# untitled2.net
KiCad netlist of a schematic drawn in EAGLE
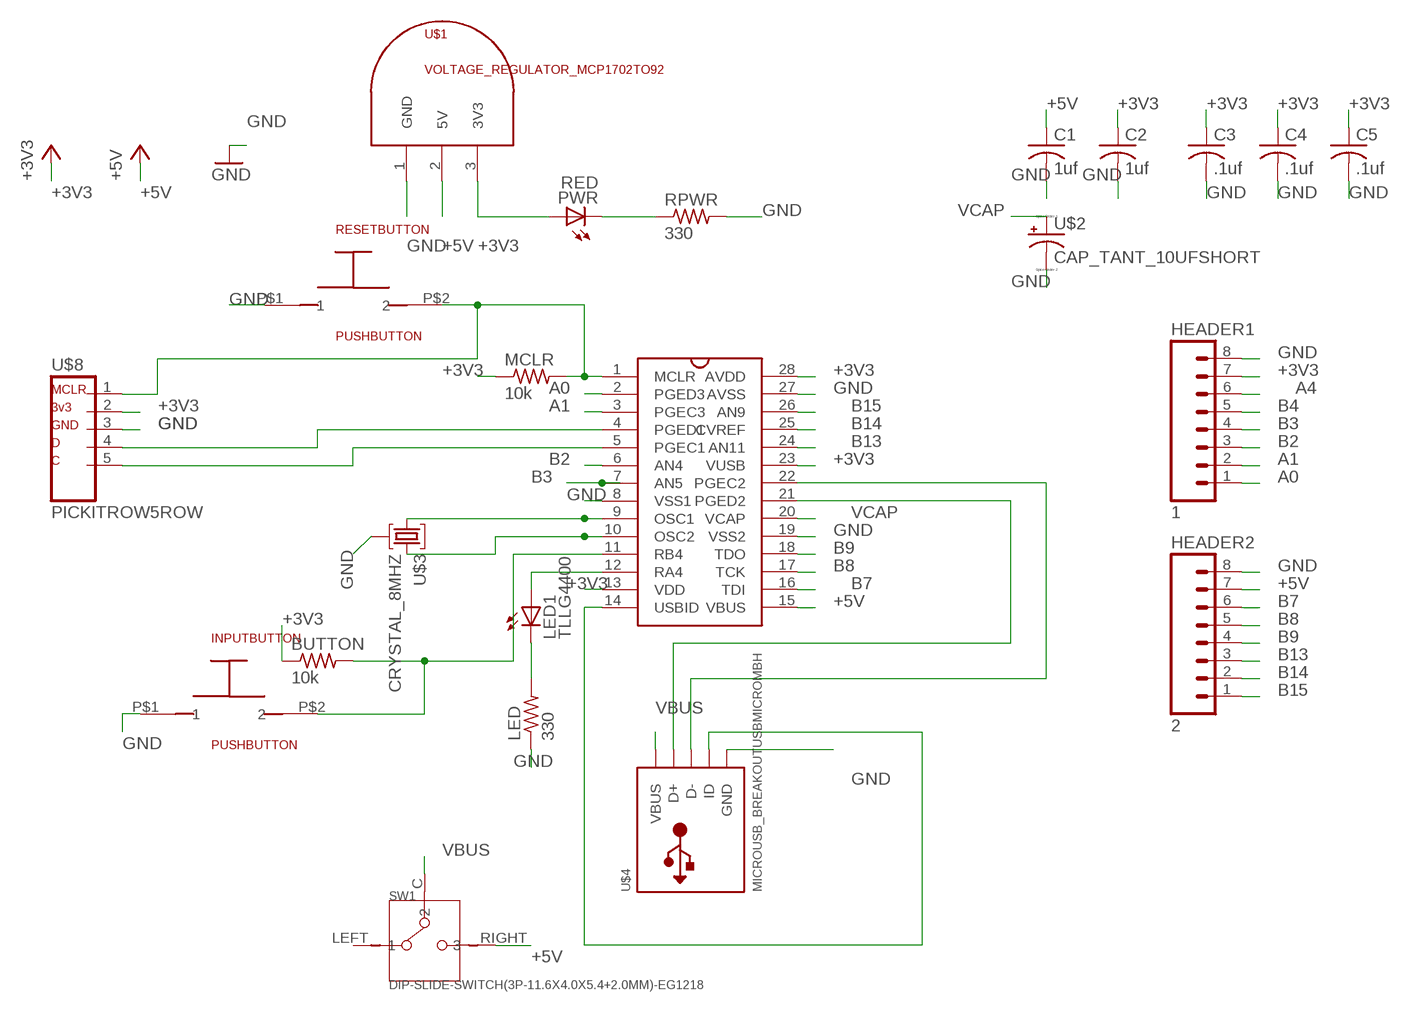
[diagram p0: schematic, sheet 1]

(export (version "E")
  (design (tool "Eeschema 10.0.6"))
  (components
    (comp (ref "BUTTON")
      (value "10k")
      (footprint "eagle-import:0207_10")
      (libsource (lib "eagle-import") (part "R-US_0207/10"))
    )
    (comp (ref "C1")
      (value "1uf")
      (footprint "eagle-import:C025-030X050")
      (libsource (lib "eagle-import") (part "C-US025-030X050"))
    )
    (comp (ref "C2")
      (value "1uf")
      (footprint "eagle-import:C025-030X050")
      (libsource (lib "eagle-import") (part "C-US025-030X050"))
    )
    (comp (ref "C3")
      (value ".1uf")
      (footprint "eagle-import:C025-030X050")
      (libsource (lib "eagle-import") (part "C-US025-030X050"))
    )
    (comp (ref "C4")
      (value ".1uf")
      (footprint "eagle-import:C025-030X050")
      (libsource (lib "eagle-import") (part "C-US025-030X050"))
    )
    (comp (ref "C5")
      (value ".1uf")
      (footprint "eagle-import:C025-030X050")
      (libsource (lib "eagle-import") (part "C-US025-030X050"))
    )
    (comp (ref "HEADER1")
      (value "1")
      (footprint "eagle-import:1X08_ROUND")
      (libsource (lib "eagle-import") (part "M08"))
    )
    (comp (ref "HEADER2")
      (value "2")
      (footprint "eagle-import:1X08_ROUND")
      (libsource (lib "eagle-import") (part "M08"))
    )
    (comp (ref "INPUTBUTTON")
      (value "PUSHBUTTON")
      (footprint "eagle-import:PUSHBUTTON")
      (libsource (lib "eagle-import") (part "PUSHBUTTON"))
    )
    (comp (ref "LED")
      (value "330")
      (footprint "eagle-import:0207_10")
      (libsource (lib "eagle-import") (part "R-US_0207/10"))
    )
    (comp (ref "LED1")
      (value "TLLG4400")
      (footprint "eagle-import:LED3MM")
      (fields (field (name "MF") "VISHAY SEMICONDUCTOR"))
      (libsource (lib "eagle-import") (part "TLLG4400"))
    )
    (comp (ref "MCLR")
      (value "10k")
      (footprint "eagle-import:0207_10")
      (libsource (lib "eagle-import") (part "R-US_0207/10"))
    )
    (comp (ref "PWR")
      (value "RED")
      (footprint "eagle-import:LED3MM")
      (libsource (lib "eagle-import") (part "LED3MM"))
    )
    (comp (ref "RESETBUTTON")
      (value "PUSHBUTTON")
      (footprint "eagle-import:PUSHBUTTON")
      (libsource (lib "eagle-import") (part "PUSHBUTTON"))
    )
    (comp (ref "RPWR")
      (value "330")
      (footprint "eagle-import:0207_10")
      (libsource (lib "eagle-import") (part "R-US_0207/10"))
    )
    (comp (ref "SW1")
      (value "DIP-SLIDE-SWITCH(3P-11.6X4.0X5.4+2.0MM)-EG1218")
      (footprint "eagle-import:SW3-2.5-11.6X4.0X5.4+2.0MM")
      (libsource (lib "eagle-import") (part "DIP-SLIDE-SWITCH(3P-11.6X4.0X5.4+2.0MM)-EG1218"))
    )
    (comp (ref "U$1")
      (value "VOLTAGE_REGULATOR_MCP1702TO92")
      (footprint "eagle-import:TO92")
      (libsource (lib "eagle-import") (part "VOLTAGE_REGULATOR_MCP1702TO92"))
    )
    (comp (ref "U$2")
      (value "CAP_TANT_10UFSHORT")
      (footprint "eagle-import:C025-040X050POL")
      (libsource (lib "eagle-import") (part "CAP_TANT_10UFSHORT"))
    )
    (comp (ref "U$3")
      (value "CRYSTAL_8MHZ")
      (footprint "eagle-import:CRYSTAL_8MHZ")
      (libsource (lib "eagle-import") (part "CRYSTAL_8MHZ"))
    )
    (comp (ref "U$4")
      (value "MICROUSB_BREAKOUTUSBMICROMBH")
      (footprint "eagle-import:USB-MB-H")
      (libsource (lib "eagle-import") (part "MICROUSB_BREAKOUTUSBMICROMBH"))
    )
    (comp (ref "U$5")
      (value "PIC32MX250F128B")
      (footprint "eagle-import:DIL28-3")
      (libsource (lib "eagle-import") (part "PIC32MX250F128B"))
    )
    (comp (ref "U$8")
      (value "PICKITROW5ROW")
      (footprint "eagle-import:1X05")
      (libsource (lib "eagle-import") (part "PICKITROW5ROW"))
    )
  )
  (nets
    (net (code "1") (name "+3V3") (class "Default")
      (node (ref "BUTTON") (pin "1") (pinfunction "1_1") (pintype "passive"))
      (node (ref "C2") (pin "1") (pinfunction "1_1") (pintype "passive"))
      (node (ref "C3") (pin "1") (pinfunction "1_1") (pintype "passive"))
      (node (ref "C4") (pin "1") (pinfunction "1_1") (pintype "passive"))
      (node (ref "C5") (pin "1") (pinfunction "1_1") (pintype "passive"))
      (node (ref "HEADER1") (pin "7") (pinfunction "7_7") (pintype "passive"))
      (node (ref "MCLR") (pin "1") (pinfunction "1_1") (pintype "passive"))
      (node (ref "PWR") (pin "A") (pinfunction "A_A") (pintype "passive"))
      (node (ref "U$1") (pin "3") (pinfunction "3V3_3") (pintype "bidirectional"))
      (node (ref "U$5") (pin "13") (pinfunction "VDD_13") (pintype "bidirectional"))
      (node (ref "U$5") (pin "23") (pinfunction "VUSB_23") (pintype "bidirectional"))
      (node (ref "U$5") (pin "28") (pinfunction "AVDD_28") (pintype "bidirectional"))
      (node (ref "U$8") (pin "2") (pinfunction "3V3_2") (pintype "passive"))
    )
    (net (code "2") (name "+5V") (class "Default")
      (node (ref "C1") (pin "1") (pinfunction "1_1") (pintype "passive"))
      (node (ref "HEADER2") (pin "7") (pinfunction "7_7") (pintype "passive"))
      (node (ref "SW1") (pin "RIGHT") (pinfunction "3_RIGHT") (pintype "bidirectional"))
      (node (ref "U$1") (pin "2") (pinfunction "5V_2") (pintype "bidirectional"))
      (node (ref "U$5") (pin "15") (pinfunction "VBUS_15") (pintype "bidirectional"))
    )
    (net (code "3") (name "/A0") (class "Default")
      (node (ref "HEADER1") (pin "1") (pinfunction "1_1") (pintype "passive"))
      (node (ref "U$5") (pin "2") (pinfunction "PGED3_2") (pintype "bidirectional"))
    )
    (net (code "4") (name "/A1") (class "Default")
      (node (ref "HEADER1") (pin "2") (pinfunction "2_2") (pintype "passive"))
      (node (ref "U$5") (pin "3") (pinfunction "PGEC3_3") (pintype "bidirectional"))
    )
    (net (code "5") (name "/A4") (class "Default")
      (node (ref "HEADER1") (pin "6") (pinfunction "6_6") (pintype "passive"))
      (node (ref "LED1") (pin "A") (pinfunction "A_A") (pintype "passive"))
      (node (ref "U$5") (pin "12") (pinfunction "RA4_12") (pintype "bidirectional"))
    )
    (net (code "6") (name "/B2") (class "Default")
      (node (ref "HEADER1") (pin "3") (pinfunction "3_3") (pintype "passive"))
      (node (ref "U$5") (pin "6") (pinfunction "AN4_6") (pintype "bidirectional"))
    )
    (net (code "7") (name "/B3") (class "Default")
      (node (ref "HEADER1") (pin "4") (pinfunction "4_4") (pintype "passive"))
      (node (ref "U$5") (pin "7") (pinfunction "AN5_7") (pintype "bidirectional"))
    )
    (net (code "8") (name "/B4") (class "Default")
      (node (ref "BUTTON") (pin "2") (pinfunction "2_2") (pintype "passive"))
      (node (ref "HEADER1") (pin "5") (pinfunction "5_5") (pintype "passive"))
      (node (ref "INPUTBUTTON") (pin "P$2") (pinfunction "2_P$2") (pintype "bidirectional"))
      (node (ref "U$5") (pin "11") (pinfunction "RB4_11") (pintype "bidirectional"))
    )
    (net (code "9") (name "/B7") (class "Default")
      (node (ref "HEADER2") (pin "6") (pinfunction "6_6") (pintype "passive"))
      (node (ref "U$5") (pin "16") (pinfunction "TDI_16") (pintype "bidirectional"))
    )
    (net (code "10") (name "/B8") (class "Default")
      (node (ref "HEADER2") (pin "5") (pinfunction "5_5") (pintype "passive"))
      (node (ref "U$5") (pin "17") (pinfunction "TCK_17") (pintype "bidirectional"))
    )
    (net (code "11") (name "/B9") (class "Default")
      (node (ref "HEADER2") (pin "4") (pinfunction "4_4") (pintype "passive"))
      (node (ref "U$5") (pin "18") (pinfunction "TDO_18") (pintype "bidirectional"))
    )
    (net (code "12") (name "/B13") (class "Default")
      (node (ref "HEADER2") (pin "3") (pinfunction "3_3") (pintype "passive"))
      (node (ref "U$5") (pin "24") (pinfunction "AN11_24") (pintype "bidirectional"))
    )
    (net (code "13") (name "/B14") (class "Default")
      (node (ref "HEADER2") (pin "2") (pinfunction "2_2") (pintype "passive"))
      (node (ref "U$5") (pin "25") (pinfunction "CVREF_25") (pintype "bidirectional"))
    )
    (net (code "14") (name "/B15") (class "Default")
      (node (ref "HEADER2") (pin "1") (pinfunction "1_1") (pintype "passive"))
      (node (ref "U$5") (pin "26") (pinfunction "AN9_26") (pintype "bidirectional"))
    )
    (net (code "15") (name "/VBUS") (class "Default")
      (node (ref "SW1") (pin "C") (pinfunction "2_C") (pintype "bidirectional"))
      (node (ref "U$4") (pin "VBUS") (pinfunction "VBUS_VBUS") (pintype "power_in"))
    )
    (net (code "16") (name "/VCAP") (class "Default")
      (node (ref "U$2") (pin "+") (pinfunction "+_+") (pintype "passive"))
      (node (ref "U$5") (pin "20") (pinfunction "VCAP_20") (pintype "bidirectional"))
    )
    (net (code "17") (name "GND") (class "Default")
      (node (ref "C1") (pin "2") (pinfunction "2_2") (pintype "passive"))
      (node (ref "C2") (pin "2") (pinfunction "2_2") (pintype "passive"))
      (node (ref "C3") (pin "2") (pinfunction "2_2") (pintype "passive"))
      (node (ref "C4") (pin "2") (pinfunction "2_2") (pintype "passive"))
      (node (ref "C5") (pin "2") (pinfunction "2_2") (pintype "passive"))
      (node (ref "HEADER1") (pin "8") (pinfunction "8_8") (pintype "passive"))
      (node (ref "HEADER2") (pin "8") (pinfunction "8_8") (pintype "passive"))
      (node (ref "INPUTBUTTON") (pin "P$1") (pinfunction "1_P$1") (pintype "bidirectional"))
      (node (ref "LED") (pin "1") (pinfunction "1_1") (pintype "passive"))
      (node (ref "RESETBUTTON") (pin "P$1") (pinfunction "1_P$1") (pintype "bidirectional"))
      (node (ref "RPWR") (pin "2") (pinfunction "2_2") (pintype "passive"))
      (node (ref "U$1") (pin "1") (pinfunction "GND_1") (pintype "bidirectional"))
      (node (ref "U$2") (pin "-") (pinfunction "-_-") (pintype "passive"))
      (node (ref "U$3") (pin "GND") (pinfunction "2_GND") (pintype "passive"))
      (node (ref "U$4") (pin "GND") (pinfunction "GND_GND") (pintype "power_in"))
      (node (ref "U$5") (pin "19") (pinfunction "VSS2_19") (pintype "bidirectional"))
      (node (ref "U$5") (pin "27") (pinfunction "AVSS_27") (pintype "bidirectional"))
      (node (ref "U$5") (pin "8") (pinfunction "VSS1_8") (pintype "bidirectional"))
      (node (ref "U$8") (pin "3") (pinfunction "GND_3") (pintype "passive"))
    )
    (net (code "18") (name "Net-(LED1-C)") (class "Default")
      (node (ref "LED") (pin "2") (pinfunction "2_2") (pintype "passive"))
      (node (ref "LED1") (pin "K") (pinfunction "C_K") (pintype "passive"))
    )
    (net (code "19") (name "Net-(PWR-C)") (class "Default")
      (node (ref "PWR") (pin "K") (pinfunction "C_K") (pintype "passive"))
      (node (ref "RPWR") (pin "1") (pinfunction "1_1") (pintype "passive"))
    )
    (net (code "20") (name "Net-(RESETBUTTON-2)") (class "Default")
      (node (ref "MCLR") (pin "2") (pinfunction "2_2") (pintype "passive"))
      (node (ref "RESETBUTTON") (pin "P$2") (pinfunction "2_P$2") (pintype "bidirectional"))
      (node (ref "U$5") (pin "1") (pinfunction "MCLR_1") (pintype "bidirectional"))
      (node (ref "U$8") (pin "1") (pinfunction "MCLR_1") (pintype "passive"))
    )
    (net (code "21") (name "Net-(U$3-1)") (class "Default")
      (node (ref "U$3") (pin "OSC1") (pinfunction "1_OSC1") (pintype "passive"))
      (node (ref "U$5") (pin "9") (pinfunction "OSC1_9") (pintype "bidirectional"))
    )
    (net (code "22") (name "Net-(U$3-3)") (class "Default")
      (node (ref "U$3") (pin "OSC2") (pinfunction "3_OSC2") (pintype "passive"))
      (node (ref "U$5") (pin "10") (pinfunction "OSC2_10") (pintype "bidirectional"))
    )
    (net (code "23") (name "Net-(U$5-PGEC1)") (class "Default")
      (node (ref "U$5") (pin "5") (pinfunction "PGEC1_5") (pintype "bidirectional"))
      (node (ref "U$8") (pin "5") (pinfunction "C_5") (pintype "passive"))
    )
    (net (code "24") (name "Net-(U$5-PGEC2)") (class "Default")
      (node (ref "U$4") (pin "D-") (pinfunction "D-_D-") (pintype "bidirectional"))
      (node (ref "U$5") (pin "22") (pinfunction "PGEC2_22") (pintype "bidirectional"))
    )
    (net (code "25") (name "Net-(U$5-PGED1)") (class "Default")
      (node (ref "U$5") (pin "4") (pinfunction "PGED1_4") (pintype "bidirectional"))
      (node (ref "U$8") (pin "4") (pinfunction "D_4") (pintype "passive"))
    )
    (net (code "26") (name "Net-(U$5-PGED2)") (class "Default")
      (node (ref "U$4") (pin "D+") (pinfunction "D+_D+") (pintype "bidirectional"))
      (node (ref "U$5") (pin "21") (pinfunction "PGED2_21") (pintype "bidirectional"))
    )
    (net (code "27") (name "Net-(U$5-USBID)") (class "Default")
      (node (ref "U$4") (pin "ID") (pinfunction "ID_ID") (pintype "bidirectional"))
      (node (ref "U$5") (pin "14") (pinfunction "USBID_14") (pintype "bidirectional"))
    )
    (net (code "28") (name "unconnected-(SW1-1-PadLEFT)") (class "Default")
      (node (ref "SW1") (pin "LEFT") (pinfunction "1_LEFT") (pintype "bidirectional"))
    )
  )
)
